# KNX-RELAY-8CH_V2.net
KiCad netlist of a schematic drawn in Altium Designer
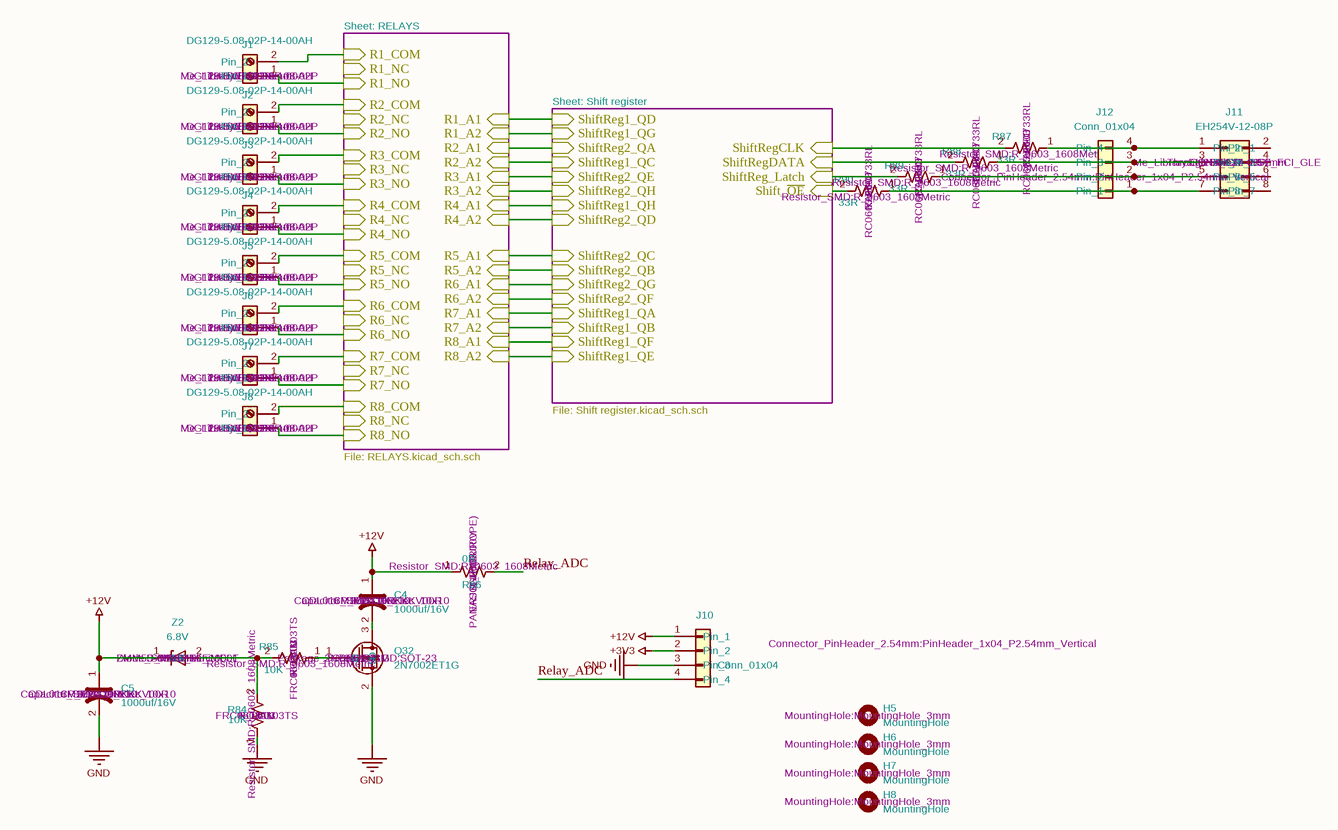
[diagram p0: KNX-RELAY-8CH_V2.SchDoc]

(export (version "E")
  (design (tool "Eeschema 10.0.6"))
  (components
    (comp (ref "C4")
      (value "1000uf/16V")
      (footprint "Capacitor_SMD:CP_Elec_10x10")
      (fields
        (field (name "MANUFACTURER PART NUMBER") "CDL016M102G10PKKKV00R")
        (field (name "MANUFACTURER") "SUSCON")
        (field (name "PACKAGE") "CP_Elec_10x10")
      )
      (libsource (lib "Device") (part "C_US"))
    )
    (comp (ref "C5")
      (value "1000uf/16V")
      (footprint "Capacitor_SMD:CP_Elec_10x10")
      (fields
        (field (name "MANUFACTURER PART NUMBER") "CDL016M102G10PKKKV00R")
        (field (name "MANUFACTURER") "SUSCON")
        (field (name "PACKAGE") "CP_Elec_10x10")
      )
      (libsource (lib "Device") (part "C_US"))
    )
    (comp (ref "H5")
      (value "MountingHole")
      (footprint "MountingHole:MountingHole_3mm")
      (libsource (lib "Mechanical") (part "MountingHole"))
    )
    (comp (ref "H6")
      (value "MountingHole")
      (footprint "MountingHole:MountingHole_3mm")
      (libsource (lib "Mechanical") (part "MountingHole"))
    )
    (comp (ref "H7")
      (value "MountingHole")
      (footprint "MountingHole:MountingHole_3mm")
      (libsource (lib "Mechanical") (part "MountingHole"))
    )
    (comp (ref "H8")
      (value "MountingHole")
      (footprint "MountingHole:MountingHole_3mm")
      (libsource (lib "Mechanical") (part "MountingHole"))
    )
    (comp (ref "J1")
      (value "DG129-5.08-02P-14-00AH")
      (footprint "Me_Library:DG129-5.08-02P")
      (fields
        (field (name "MANUFACTURER PART NUMBER") "DG129-5.08-02P-14-00AH")
        (field (name "MANUFACTURER") "DEGSON")
        (field (name "PACKAGE") "THT V/T  5.08mm")
      )
      (libsource (lib "Connector") (part "Screw_Terminal_01x02"))
    )
    (comp (ref "J2")
      (value "DG129-5.08-02P-14-00AH")
      (footprint "Me_Library:DG129-5.08-02P")
      (fields
        (field (name "MANUFACTURER PART NUMBER") "DG129-5.08-02P-14-00AH")
        (field (name "MANUFACTURER") "DEGSON")
        (field (name "PACKAGE") "THT V/T  5.08mm")
      )
      (libsource (lib "Connector") (part "Screw_Terminal_01x02"))
    )
    (comp (ref "J3")
      (value "DG129-5.08-02P-14-00AH")
      (footprint "Me_Library:DG129-5.08-02P")
      (fields
        (field (name "MANUFACTURER PART NUMBER") "DG129-5.08-02P-14-00AH")
        (field (name "MANUFACTURER") "DEGSON")
        (field (name "PACKAGE") "THT V/T  5.08mm")
      )
      (libsource (lib "Connector") (part "Screw_Terminal_01x02"))
    )
    (comp (ref "J4")
      (value "DG129-5.08-02P-14-00AH")
      (footprint "Me_Library:DG129-5.08-02P")
      (fields
        (field (name "MANUFACTURER PART NUMBER") "DG129-5.08-02P-14-00AH")
        (field (name "MANUFACTURER") "DEGSON")
        (field (name "PACKAGE") "THT V/T  5.08mm")
      )
      (libsource (lib "Connector") (part "Screw_Terminal_01x02"))
    )
    (comp (ref "J5")
      (value "DG129-5.08-02P-14-00AH")
      (footprint "Me_Library:DG129-5.08-02P")
      (fields
        (field (name "MANUFACTURER PART NUMBER") "DG129-5.08-02P-14-00AH")
        (field (name "MANUFACTURER") "DEGSON")
        (field (name "PACKAGE") "THT V/T  5.08mm")
      )
      (libsource (lib "Connector") (part "Screw_Terminal_01x02"))
    )
    (comp (ref "J6")
      (value "DG129-5.08-02P-14-00AH")
      (footprint "Me_Library:DG129-5.08-02P")
      (fields
        (field (name "MANUFACTURER PART NUMBER") "DG129-5.08-02P-14-00AH")
        (field (name "MANUFACTURER") "DEGSON")
        (field (name "PACKAGE") "THT V/T  5.08mm")
      )
      (libsource (lib "Connector") (part "Screw_Terminal_01x02"))
    )
    (comp (ref "J7")
      (value "DG129-5.08-02P-14-00AH")
      (footprint "Me_Library:DG129-5.08-02P")
      (fields
        (field (name "MANUFACTURER PART NUMBER") "DG129-5.08-02P-14-00AH")
        (field (name "MANUFACTURER") "DEGSON")
        (field (name "PACKAGE") "THT V/T  5.08mm")
      )
      (libsource (lib "Connector") (part "Screw_Terminal_01x02"))
    )
    (comp (ref "J8")
      (value "DG129-5.08-02P-14-00AH")
      (footprint "Me_Library:DG129-5.08-02P")
      (fields
        (field (name "MANUFACTURER PART NUMBER") "DG129-5.08-02P-14-00AH")
        (field (name "MANUFACTURER") "DEGSON")
        (field (name "PACKAGE") "THT V/T  5.08mm")
      )
      (libsource (lib "Connector") (part "Screw_Terminal_01x02"))
    )
    (comp (ref "J10")
      (value "Conn_01x04")
      (footprint "Connector_PinHeader_2.54mm:PinHeader_1x04_P2.54mm_Vertical")
      (description "FEMALE HEADER 4PIN(1x4) 2.54mm THT V/T TRAY")
      (fields
        (field (name "MANUFACTURER PART NUMBER") "5PS1SDA85-104G0NNNAL-00")
        (field (name "MANUFACTURER") "AMTEK")
      )
      (libsource (lib "Connector_Generic") (part "Conn_01x04"))
    )
    (comp (ref "J11")
      (value "EH254V-12-08P")
      (footprint "Me_Library:CON8_2X4_USZ_FCI_GLE")
      (fields
        (field (name "MANUFACTURER PART NUMBER") "EH254V-12-08P")
        (field (name "MANUFACTURER") "XFCN")
        (field (name "PACKAGE") "Through Hole,P=2.54mm")
      )
      (libsource (lib "Connector_Generic") (part "Conn_02x04_Odd_Even"))
    )
    (comp (ref "J12")
      (value "Conn_01x04")
      (footprint "Connector_PinHeader_2.54mm:PinHeader_1x04_P2.54mm_Vertical")
      (description "FEMALE HEADER 4PIN(1x4) 2.54mm THT V/T TRAY")
      (fields
        (field (name "MANUFACTURER PART NUMBER") "5PS1SDA85-104G0NNNAL-00")
        (field (name "MANUFACTURER") "AMTEK")
      )
      (libsource (lib "") (part "Conn_01x04_1"))
    )
    (comp (ref "Q32")
      (value "2N7002ET1G")
      (footprint "Package_TO_SOT_SMD:SOT-23")
      (fields
        (field (name "MANUFACTURER PART NUMBER") "2N7002ET1G")
        (field (name "MANUFACTURER") "onsemi")
        (field (name "PACKAGE") "SOT-23")
      )
      (libsource (lib "Transistor_FET_Other") (part "Q_NMOS_Depletion_GSD"))
    )
    (comp (ref "R84")
      (value "10K")
      (footprint "Resistor_SMD:R_0603_1608Metric")
      (fields
        (field (name "MANUFACTURER PART NUMBER") "FRC0603J103TS")
        (field (name "MANUFACTURER") "FOJAN")
        (field (name "PACKAGE") "R_0603")
      )
      (libsource (lib "Device") (part "R_US"))
    )
    (comp (ref "R85")
      (value "10K")
      (footprint "Resistor_SMD:R_0603_1608Metric")
      (fields
        (field (name "MANUFACTURER PART NUMBER") "FRC0603J103TS")
        (field (name "MANUFACTURER") "FOJAN")
        (field (name "PACKAGE") "R_0603")
      )
      (libsource (lib "Device") (part "R_US"))
    )
    (comp (ref "R86")
      (value "0R")
      (footprint "Resistor_SMD:R_0603_1608Metric")
      (description "RES.(1608) 0603 0 Ohms 1/10W JUMPER")
      (fields
        (field (name "MANUFACTURER PART NUMBER") "ERJ3GEY0R00V")
        (field (name "MANUFACTURER") "PANASONIC(EUROPE)")
        (field (name "PACKAGE") "R_0603")
        (field (name "Comment") "ERJ3GEY0R00V")
      )
      (libsource (lib "Device") (part "R_US"))
    )
    (comp (ref "R87")
      (value "33R")
      (footprint "Resistor_SMD:R_0603_1608Metric")
      (fields
        (field (name "MANUFACTURER PART NUMBER") "RC0603JR-0733RL")
        (field (name "MANUFACTURER") "YAGEO")
        (field (name "PACKAGE") "R_0603")
      )
      (libsource (lib "Device") (part "R_US"))
    )
    (comp (ref "R88")
      (value "33R")
      (footprint "Resistor_SMD:R_0603_1608Metric")
      (fields
        (field (name "MANUFACTURER PART NUMBER") "RC0603JR-0733RL")
        (field (name "MANUFACTURER") "YAGEO")
        (field (name "PACKAGE") "R_0603")
      )
      (libsource (lib "Device") (part "R_US"))
    )
    (comp (ref "R89")
      (value "33R")
      (footprint "Resistor_SMD:R_0603_1608Metric")
      (fields
        (field (name "MANUFACTURER PART NUMBER") "RC0603JR-0733RL")
        (field (name "MANUFACTURER") "YAGEO")
        (field (name "PACKAGE") "R_0603")
      )
      (libsource (lib "Device") (part "R_US"))
    )
    (comp (ref "R90")
      (value "33R")
      (footprint "Resistor_SMD:R_0603_1608Metric")
      (fields
        (field (name "MANUFACTURER PART NUMBER") "RC0603JR-0733RL")
        (field (name "MANUFACTURER") "YAGEO")
        (field (name "PACKAGE") "R_0603")
      )
      (libsource (lib "Device") (part "R_US"))
    )
    (comp (ref "Z2")
      (value "6.8V")
      (footprint "Diode_SMD:D_MiniMELF")
      (fields
        (field (name "MANUFACTURER PART NUMBER") "ZMM55-C6V8_R1_10001")
        (field (name "MANUFACTURER") "PANJIT")
        (field (name "PACKAGE") "D_MiniMELF")
      )
      (libsource (lib "Device") (part "D_Zener"))
    )
  )
  (nets
    (net (code "1") (name "+3V3") (class "Default")
      (node (ref "J10") (pin "2") (pinfunction "Pin_2_2") (pintype "passive"))
    )
    (net (code "2") (name "+12V") (class "Default")
      (node (ref "C4") (pin "1") (pinfunction "1_1") (pintype "passive"))
      (node (ref "C5") (pin "1") (pinfunction "1_1") (pintype "passive"))
      (node (ref "J10") (pin "1") (pinfunction "Pin_1_1") (pintype "passive"))
      (node (ref "R86") (pin "1") (pinfunction "1_1") (pintype "passive"))
      (node (ref "Z2") (pin "1") (pinfunction "K_1") (pintype "passive"))
    )
    (net (code "5") (name "/R1_COM") (class "Default")
      (node (ref "J1") (pin "2") (pinfunction "Pin_2_2") (pintype "passive"))
    )
    (net (code "7") (name "/R1_NO") (class "Default")
      (node (ref "J1") (pin "1") (pinfunction "Pin_1_1") (pintype "passive"))
    )
    (net (code "10") (name "/R2_COM") (class "Default")
      (node (ref "J2") (pin "2") (pinfunction "Pin_2_2") (pintype "passive"))
    )
    (net (code "12") (name "/R2_NO") (class "Default")
      (node (ref "J2") (pin "1") (pinfunction "Pin_1_1") (pintype "passive"))
    )
    (net (code "15") (name "/R3_COM") (class "Default")
      (node (ref "J3") (pin "2") (pinfunction "Pin_2_2") (pintype "passive"))
    )
    (net (code "17") (name "/R3_NO") (class "Default")
      (node (ref "J3") (pin "1") (pinfunction "Pin_1_1") (pintype "passive"))
    )
    (net (code "20") (name "/R4_COM") (class "Default")
      (node (ref "J4") (pin "2") (pinfunction "Pin_2_2") (pintype "passive"))
    )
    (net (code "22") (name "/R4_NO") (class "Default")
      (node (ref "J4") (pin "1") (pinfunction "Pin_1_1") (pintype "passive"))
    )
    (net (code "25") (name "/R5_COM") (class "Default")
      (node (ref "J5") (pin "2") (pinfunction "Pin_2_2") (pintype "passive"))
    )
    (net (code "27") (name "/R5_NO") (class "Default")
      (node (ref "J5") (pin "1") (pinfunction "Pin_1_1") (pintype "passive"))
    )
    (net (code "30") (name "/R6_COM") (class "Default")
      (node (ref "J6") (pin "2") (pinfunction "Pin_2_2") (pintype "passive"))
    )
    (net (code "32") (name "/R6_NO") (class "Default")
      (node (ref "J6") (pin "1") (pinfunction "Pin_1_1") (pintype "passive"))
    )
    (net (code "35") (name "/R7_COM") (class "Default")
      (node (ref "J7") (pin "2") (pinfunction "Pin_2_2") (pintype "passive"))
    )
    (net (code "37") (name "/R7_NO") (class "Default")
      (node (ref "J7") (pin "1") (pinfunction "Pin_1_1") (pintype "passive"))
    )
    (net (code "40") (name "/R8_COM") (class "Default")
      (node (ref "J8") (pin "2") (pinfunction "Pin_2_2") (pintype "passive"))
    )
    (net (code "42") (name "/R8_NO") (class "Default")
      (node (ref "J8") (pin "1") (pinfunction "Pin_1_1") (pintype "passive"))
    )
    (net (code "43") (name "/Relay_ADC") (class "Default")
      (node (ref "J10") (pin "4") (pinfunction "Pin_4_4") (pintype "passive"))
      (node (ref "R86") (pin "2") (pinfunction "2_2") (pintype "passive"))
    )
    (net (code "44") (name "/ShiftRegCLK") (class "Default")
      (node (ref "R87") (pin "2") (pinfunction "2_2") (pintype "passive"))
    )
    (net (code "45") (name "/ShiftRegDATA") (class "Default")
      (node (ref "R88") (pin "2") (pinfunction "2_2") (pintype "passive"))
    )
    (net (code "46") (name "/ShiftReg_Latch") (class "Default")
      (node (ref "R89") (pin "2") (pinfunction "2_2") (pintype "passive"))
    )
    (net (code "47") (name "/Shift_~{OE}") (class "Default")
      (node (ref "R90") (pin "2") (pinfunction "2_2") (pintype "passive"))
    )
    (net (code "48") (name "GND") (class "Default")
      (node (ref "C5") (pin "2") (pinfunction "2_2") (pintype "passive"))
      (node (ref "J10") (pin "3") (pinfunction "Pin_3_3") (pintype "passive"))
      (node (ref "Q32") (pin "2") (pinfunction "S_2") (pintype "passive"))
      (node (ref "R84") (pin "1") (pinfunction "1_1") (pintype "passive"))
    )
    (net (code "49") (name "Net-(J11-Pin_1)") (class "Default")
      (node (ref "J11") (pin "1") (pinfunction "Pin_1_1") (pintype "passive"))
      (node (ref "J12") (pin "4") (pinfunction "Pin_4_4") (pintype "passive"))
      (node (ref "R87") (pin "1") (pinfunction "1_1") (pintype "passive"))
    )
    (net (code "50") (name "Net-(J11-Pin_3)") (class "Default")
      (node (ref "J11") (pin "3") (pinfunction "Pin_3_3") (pintype "passive"))
      (node (ref "J12") (pin "3") (pinfunction "Pin_3_3") (pintype "passive"))
      (node (ref "R88") (pin "1") (pinfunction "1_1") (pintype "passive"))
    )
    (net (code "51") (name "Net-(J11-Pin_5)") (class "Default")
      (node (ref "J11") (pin "5") (pinfunction "Pin_5_5") (pintype "passive"))
      (node (ref "J12") (pin "2") (pinfunction "Pin_2_2") (pintype "passive"))
      (node (ref "R89") (pin "1") (pinfunction "1_1") (pintype "passive"))
    )
    (net (code "52") (name "Net-(J11-Pin_7)") (class "Default")
      (node (ref "J11") (pin "7") (pinfunction "Pin_7_7") (pintype "passive"))
      (node (ref "J12") (pin "1") (pinfunction "Pin_1_1") (pintype "passive"))
      (node (ref "R90") (pin "1") (pinfunction "1_1") (pintype "passive"))
    )
    (net (code "53") (name "Net-(Q32-D)") (class "Default")
      (node (ref "C4") (pin "2") (pinfunction "2_2") (pintype "passive"))
      (node (ref "Q32") (pin "3") (pinfunction "D_3") (pintype "passive"))
    )
    (net (code "54") (name "Net-(Q32-G)") (class "Default")
      (node (ref "Q32") (pin "1") (pinfunction "G_1") (pintype "passive"))
      (node (ref "R85") (pin "1") (pinfunction "1_1") (pintype "passive"))
    )
    (net (code "55") (name "Net-(Z2-A)") (class "Default")
      (node (ref "R84") (pin "2") (pinfunction "2_2") (pintype "passive"))
      (node (ref "R85") (pin "2") (pinfunction "2_2") (pintype "passive"))
      (node (ref "Z2") (pin "2") (pinfunction "A_2") (pintype "passive"))
    )
    (net (code "56") (name "unconnected-(J11-Pin_2-Pad2)") (class "Default")
      (node (ref "J11") (pin "2") (pinfunction "Pin_2_2") (pintype "passive"))
    )
    (net (code "57") (name "unconnected-(J11-Pin_4-Pad4)") (class "Default")
      (node (ref "J11") (pin "4") (pinfunction "Pin_4_4") (pintype "passive"))
    )
    (net (code "58") (name "unconnected-(J11-Pin_6-Pad6)") (class "Default")
      (node (ref "J11") (pin "6") (pinfunction "Pin_6_6") (pintype "passive"))
    )
    (net (code "59") (name "unconnected-(J11-Pin_8-Pad8)") (class "Default")
      (node (ref "J11") (pin "8") (pinfunction "Pin_8_8") (pintype "passive"))
    )
  )
)
